# JTAG_Connector.net
KiCad netlist of a schematic drawn in Altium Designer
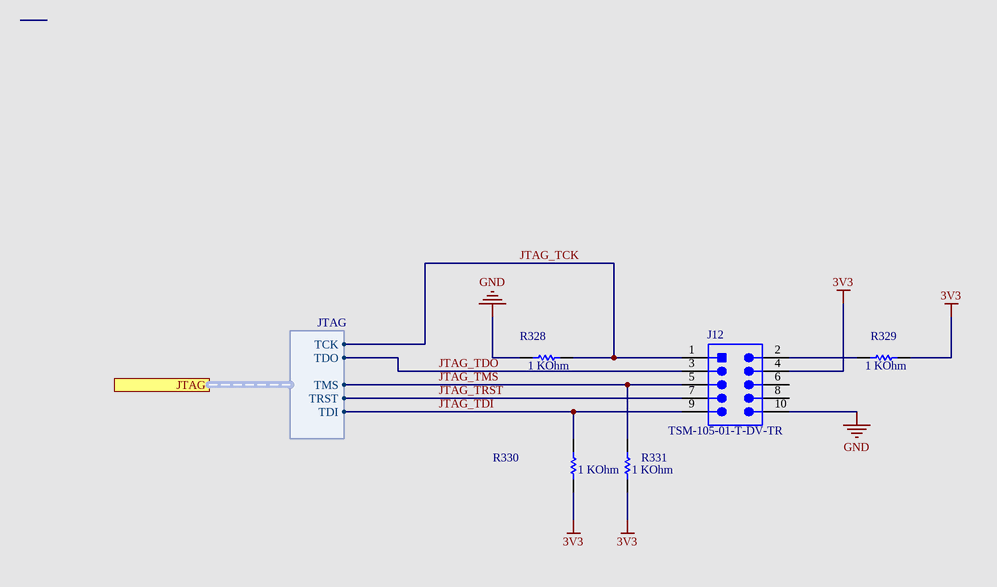
[diagram p0: JTAG_Connector.SchDoc]

(export (version "E")
  (design (tool "Eeschema 10.0.6"))
  (components
    (comp (ref "J12")
      (value "TSM-105-01-T-DV-TR")
      (footprint "SMTC-TSM-105-01-T-DV_V")
      (description "Male Header, Pitch 2.54 mm, 2 x 5 Position, Height 9.65 mm, -55 to 105 degC, RoHS, Tape and Reel")
      (libsource (lib "Altium Content Vault") (part "CN-2P-M-R10"))
    )
    (comp (ref "R328")
      (value "ERJ-2RKF1001X")
      (footprint "RESC1005X40X25LL05T05")
      (description "Chip Resistor, 1 KOhm, +/- 1%, 100 mW, -55 to 155 degC, 0402 (1005 Metric), RoHS, Tape and Reel")
      (fields
        (field (name "RESISTANCE") "1 KOhm")
        (field (name "TOLERANCE") "1%")
        (field (name "MANUFACTURER") "Basic Passives")
      )
      (libsource (lib "Altium Content Vault") (part "CMP-2002-00606-3"))
    )
    (comp (ref "R329")
      (value "ERJ-2RKF1001X")
      (footprint "RESC1005X40X25LL05T05")
      (description "Chip Resistor, 1 KOhm, +/- 1%, 100 mW, -55 to 155 degC, 0402 (1005 Metric), RoHS, Tape and Reel")
      (fields
        (field (name "RESISTANCE") "1 KOhm")
        (field (name "TOLERANCE") "1%")
        (field (name "MANUFACTURER") "Basic Passives")
      )
      (libsource (lib "Altium Content Vault") (part "RES-2"))
    )
    (comp (ref "R330")
      (value "ERJ-2RKF1001X")
      (footprint "RESC1005X40X25LL05T05")
      (description "Chip Resistor, 1 KOhm, +/- 1%, 100 mW, -55 to 155 degC, 0402 (1005 Metric), RoHS, Tape and Reel")
      (fields
        (field (name "RESISTANCE") "1 KOhm")
        (field (name "TOLERANCE") "1%")
        (field (name "MANUFACTURER") "Basic Passives")
      )
      (libsource (lib "Altium Content Vault") (part "RES-2"))
    )
    (comp (ref "R331")
      (value "ERJ-2RKF1001X")
      (footprint "RESC1005X40X25LL05T05")
      (description "Chip Resistor, 1 KOhm, +/- 1%, 100 mW, -55 to 155 degC, 0402 (1005 Metric), RoHS, Tape and Reel")
      (fields
        (field (name "RESISTANCE") "1 KOhm")
        (field (name "TOLERANCE") "1%")
        (field (name "MANUFACTURER") "Basic Passives")
      )
      (libsource (lib "Altium Content Vault") (part "RES-2"))
    )
  )
  (nets
    (net (code "2") (name "/JTAG_TCK") (class "Default")
      (node (ref "J12") (pin "1") (pinfunction "1_1") (pintype "passive"))
      (node (ref "R328") (pin "2") (pinfunction "2_2") (pintype "passive"))
    )
    (net (code "3") (name "/JTAG_TDI") (class "Default")
      (node (ref "J12") (pin "9") (pinfunction "9_9") (pintype "passive"))
      (node (ref "R330") (pin "2") (pinfunction "2_2") (pintype "passive"))
    )
    (net (code "4") (name "/JTAG_TDO") (class "Default")
      (node (ref "J12") (pin "3") (pinfunction "3_3") (pintype "passive"))
    )
    (net (code "5") (name "/JTAG_TMS") (class "Default")
      (node (ref "J12") (pin "5") (pinfunction "5_5") (pintype "passive"))
      (node (ref "R331") (pin "2") (pinfunction "2_2") (pintype "passive"))
    )
    (net (code "6") (name "/JTAG_TRST") (class "Default")
      (node (ref "J12") (pin "7") (pinfunction "7_7") (pintype "passive"))
    )
    (net (code "8") (name "3V3") (class "Default")
      (node (ref "J12") (pin "4") (pinfunction "4_4") (pintype "passive"))
      (node (ref "R329") (pin "2") (pinfunction "2_2") (pintype "passive"))
      (node (ref "R330") (pin "1") (pinfunction "1_1") (pintype "passive"))
      (node (ref "R331") (pin "1") (pinfunction "1_1") (pintype "passive"))
    )
    (net (code "9") (name "GND") (class "Default")
      (node (ref "J12") (pin "10") (pinfunction "10_10") (pintype "passive"))
      (node (ref "R328") (pin "1") (pinfunction "1_1") (pintype "passive"))
    )
    (net (code "10") (name "Net-(J12-Pad2)") (class "Default")
      (node (ref "J12") (pin "2") (pinfunction "2_2") (pintype "passive"))
      (node (ref "R329") (pin "1") (pinfunction "1_1") (pintype "passive"))
    )
    (net (code "11") (name "unconnected-(J12-Pad6)") (class "Default")
      (node (ref "J12") (pin "6") (pinfunction "6_6") (pintype "passive"))
    )
    (net (code "12") (name "unconnected-(J12-Pad8)") (class "Default")
      (node (ref "J12") (pin "8") (pinfunction "8_8") (pintype "passive"))
    )
  )
)
